# 1_MIAN.net
KiCad netlist of a schematic drawn in Altium Designer
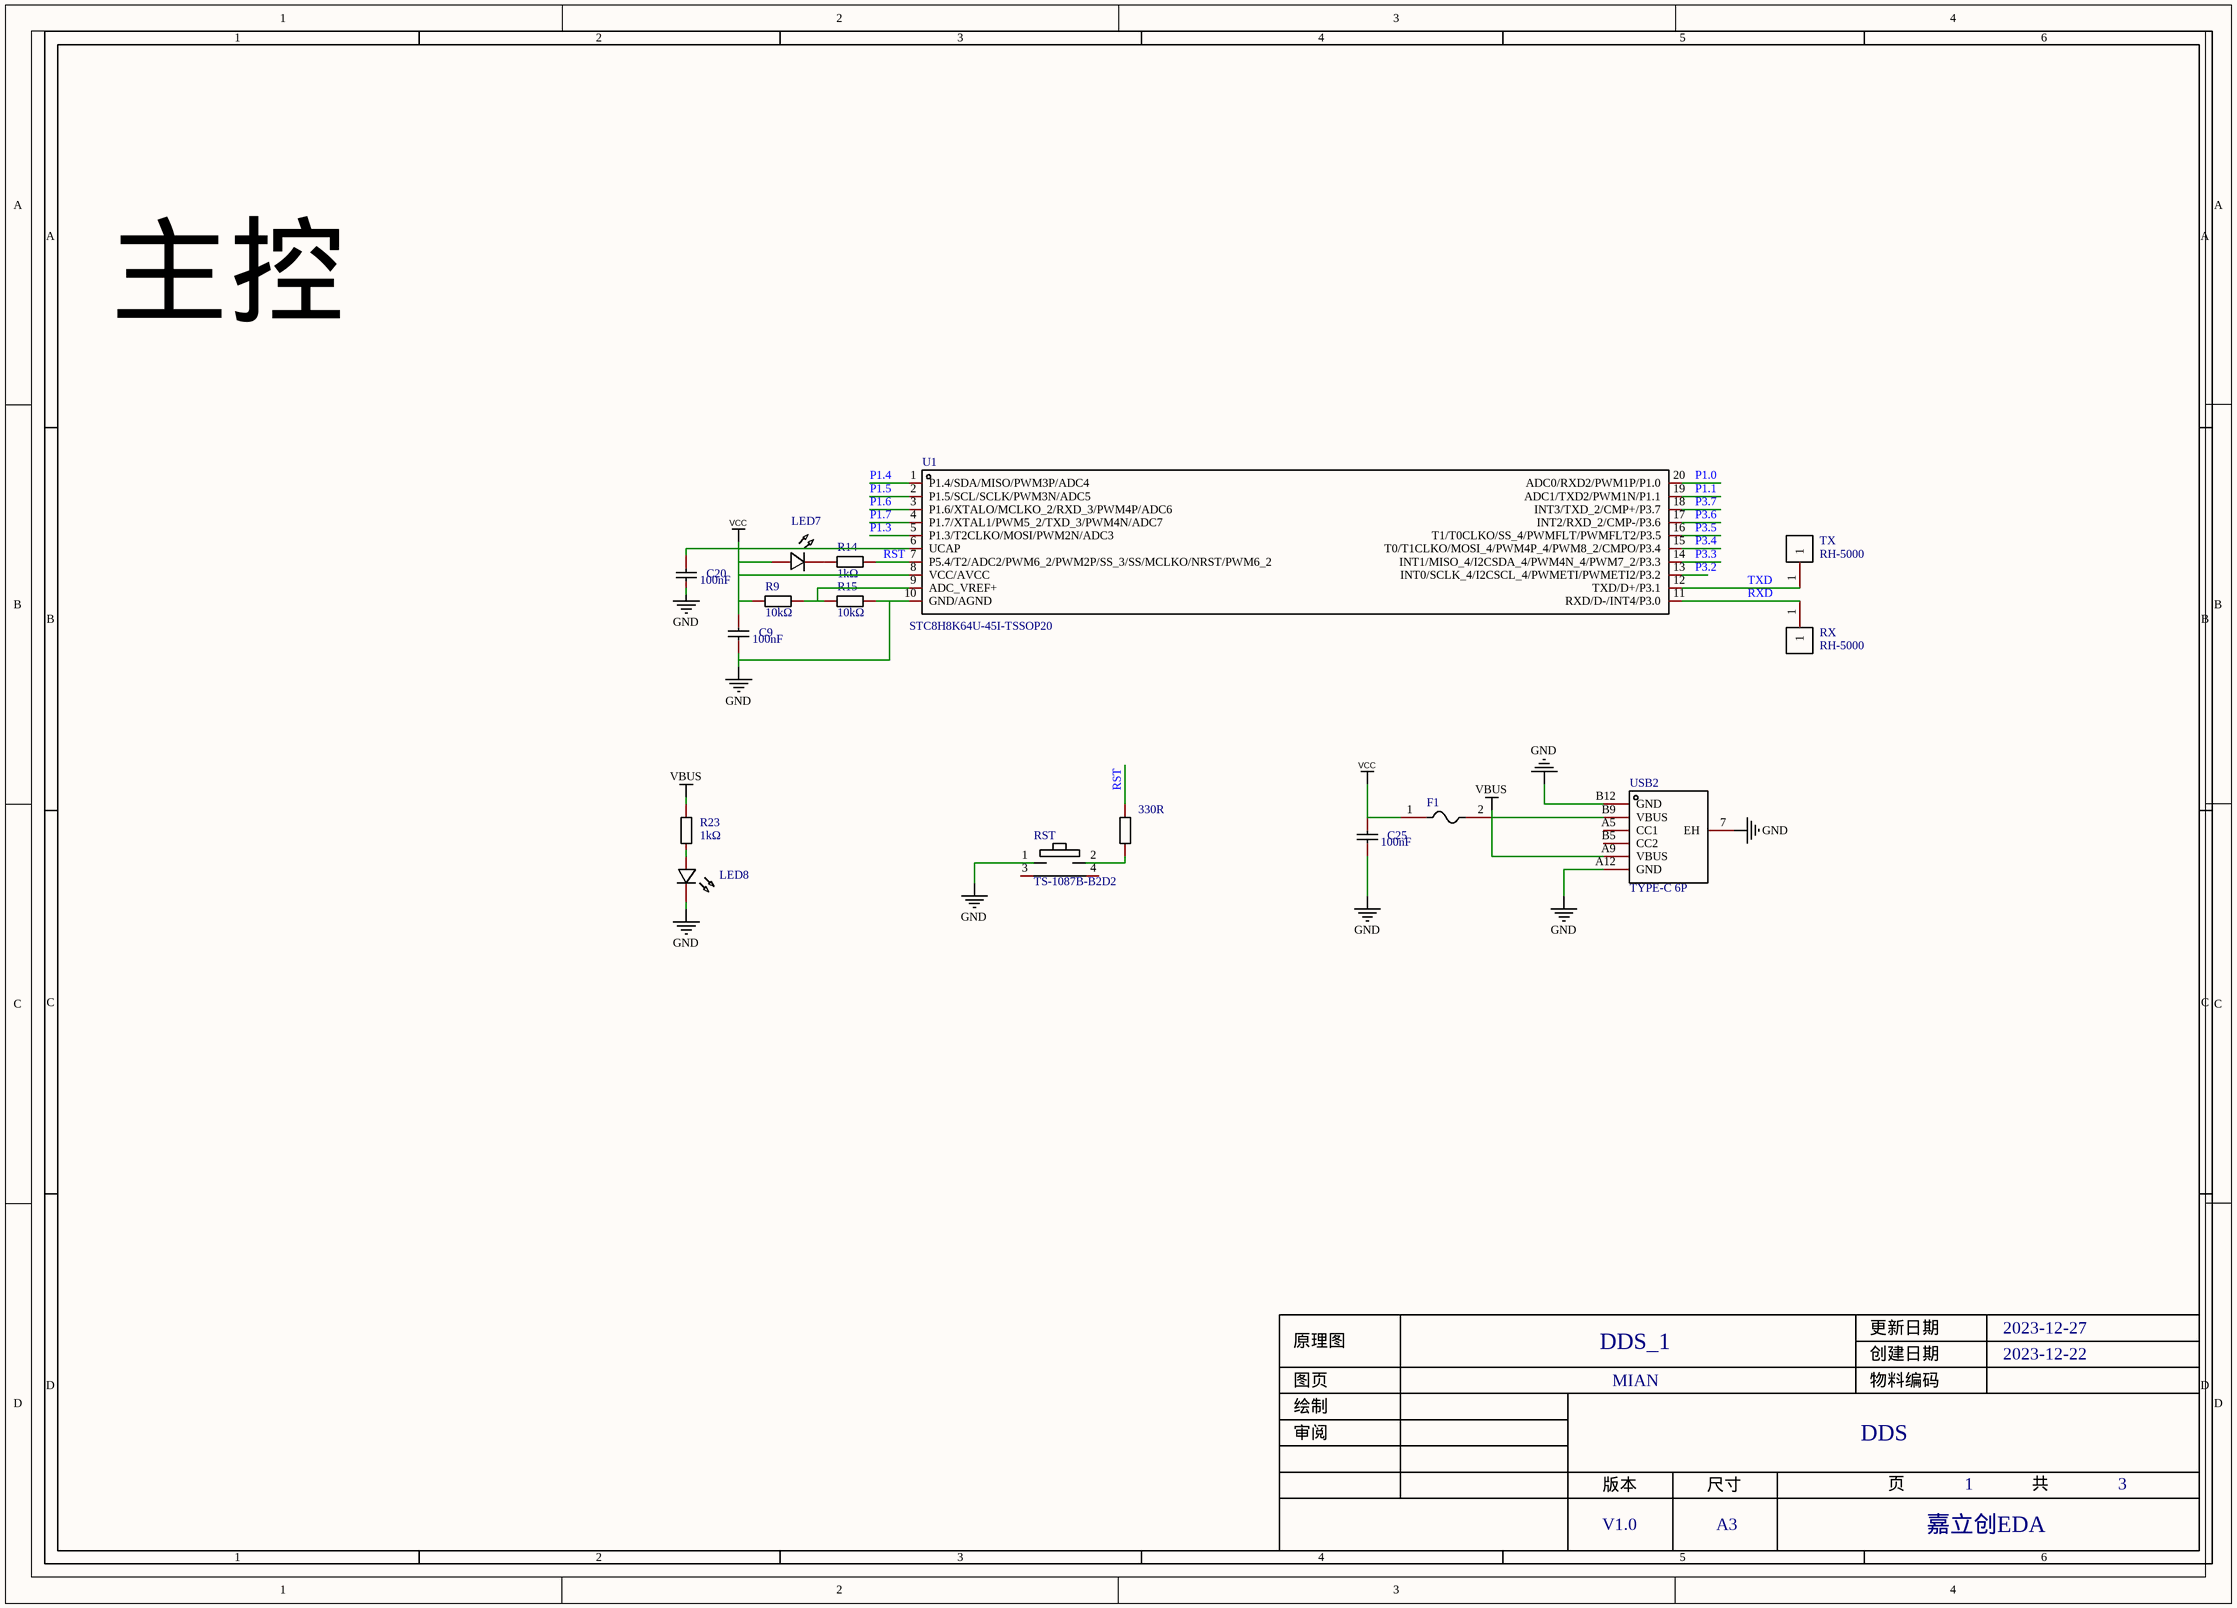
[diagram p0: 1_MIAN.schdoc]

(export (version "E")
  (design (tool "Eeschema 10.0.6"))
  (components
    (comp (ref "C9")
      (value "100nF")
      (description "容值:100nF;精度:±10%;额定电压:50V;材质(温度系数):X7R;")
      (fields
        (field (name "NAME") "100nF")
        (field (name "MANUFACTURER") "FH(风华)")
        (field (name "MANUFACTURER PART") "0805B104K500NT")
      )
      (libsource (lib "altium-import") (part "root_1_0805B104K500NT_"))
    )
    (comp (ref "C20")
      (value "100nF")
      (description "容值:100nF;精度:±10%;额定电压:50V;材质(温度系数):X7R;")
      (fields
        (field (name "NAME") "100nF")
        (field (name "MANUFACTURER") "FH(风华)")
        (field (name "MANUFACTURER PART") "0805B104K500NT")
      )
      (libsource (lib "altium-import") (part "root_1_0805B104K500NT_"))
    )
    (comp (ref "C25")
      (value "100nF")
      (description "容值:100nF;精度:±10%;额定电压:50V;材质(温度系数):X7R;")
      (fields
        (field (name "NAME") "100nF")
        (field (name "MANUFACTURER") "FH(风华)")
        (field (name "MANUFACTURER PART") "0805B104K500NT")
      )
      (libsource (lib "altium-import") (part "root_1_0805B104K500NT_"))
    )
    (comp (ref "F1")
      (value "nSMD010")
      (description "最大电压:60V;最大电流:40A;保持电流:100mA;跳闸电流:250mA;")
      (fields (field (name "MANUFACTURER") "台湾陆海"))
      (libsource (lib "altium-import") (part "root_0_nSMD010_"))
    )
    (comp (ref "LED7") (value "LED_B") (libsource (lib "altium-import") (part "root_0_LED_B_")))
    (comp (ref "LED8") (value "LED_B") (libsource (lib "altium-import") (part "root_3_LED_B_")))
    (comp (ref "R5")
      (value "330R")
      (description "阻值:1kΩ;精度:±1%;功率:125mW;温度系数:±100ppm/℃;电阻类型:厚膜电阻;")
      (fields
        (field (name "MANUFACTURER") "UNI-ROYAL(厚声)")
        (field (name "MANUFACTURER PART") "0805W8F1001T5E")
      )
      (libsource (lib "altium-import") (part "root_1_0805W8F1001T5E_"))
    )
    (comp (ref "R9")
      (value "10kΩ")
      (description "阻值:1kΩ;精度:±1%;功率:125mW;温度系数:±100ppm/℃;电阻类型:厚膜电阻;")
      (fields
        (field (name "NAME") "10kΩ")
        (field (name "MANUFACTURER") "UNI-ROYAL(厚声)")
        (field (name "MANUFACTURER PART") "0805W8F1001T5E")
      )
      (libsource (lib "altium-import") (part "root_0_0805W8F1001T5E_"))
    )
    (comp (ref "R14")
      (value "1kΩ")
      (description "阻值:1kΩ;精度:±1%;功率:125mW;温度系数:±100ppm/℃;电阻类型:厚膜电阻;")
      (fields
        (field (name "NAME") "1kΩ")
        (field (name "MANUFACTURER") "UNI-ROYAL(厚声)")
        (field (name "MANUFACTURER PART") "0805W8F1001T5E")
      )
      (libsource (lib "altium-import") (part "root_0_0805W8F1001T5E_"))
    )
    (comp (ref "R15")
      (value "10kΩ")
      (description "阻值:1kΩ;精度:±1%;功率:125mW;温度系数:±100ppm/℃;电阻类型:厚膜电阻;")
      (fields
        (field (name "NAME") "10kΩ")
        (field (name "MANUFACTURER") "UNI-ROYAL(厚声)")
        (field (name "MANUFACTURER PART") "0805W8F1001T5E")
      )
      (libsource (lib "altium-import") (part "root_0_0805W8F1001T5E_"))
    )
    (comp (ref "R23")
      (value "1kΩ")
      (description "阻值:1kΩ;精度:±1%;功率:125mW;温度系数:±100ppm/℃;电阻类型:厚膜电阻;")
      (fields
        (field (name "NAME") "1kΩ")
        (field (name "MANUFACTURER") "UNI-ROYAL(厚声)")
        (field (name "MANUFACTURER PART") "0805W8F1001T5E")
      )
      (libsource (lib "altium-import") (part "root_1_0805W8F1001T5E_"))
    )
    (comp (ref "RST")
      (value "TS-1087B-B2D2")
      (description "电路结构:单刀单掷;按钮作用方向:侧面触动;致动器样式:矩形按钮;照明颜色:-;作用力:180gf ±30gf;开关高度:3.5mm;")
      (fields (field (name "NAME") "TS-1087B-B2D2") (field (name "MANUFACTURER") "Yuandi(元迪)"))
      (libsource (lib "altium-import") (part "root_0_TS-1087B-B2D2_"))
    )
    (comp (ref "RX")
      (value "RH-5000")
      (description "100x80mm")
      (fields (field (name "NAME") "RH-5000") (field (name "MANUFACTURER") "荣和"))
      (libsource (lib "altium-import") (part "root_1_RH-5000_"))
    )
    (comp (ref "TX")
      (value "RH-5000")
      (description "100x80mm")
      (fields (field (name "NAME") "RH-5000") (field (name "MANUFACTURER") "荣和"))
      (libsource (lib "altium-import") (part "root_3_RH-5000_"))
    )
    (comp (ref "U1")
      (value "STC8H8K64U-45I-TSSOP20")
      (fields (field (name "NAME") "STC8H8K64U-45I-TSSOP20") (field (name "MANUFACTURER") "STC(宏晶)"))
      (libsource (lib "altium-import") (part "root_0_STC8H8K64U-45I-TSSOP20_"))
    )
    (comp (ref "USB2")
      (value "TYPE-C 6P")
      (description "连接器类型:Type-C;标准:-;公母:母;端口数量:1;触点数量:6P;安装方式:卧贴;额定电流 - 电源:-;工作温度范围:-40℃~+85℃;")
      (fields (field (name "NAME") "TYPE-C 6P") (field (name "MANUFACTURER") "SHOU HAN(首韩)"))
      (libsource (lib "altium-import") (part "root_0_TYPE-C 6P_"))
    )
  )
  (nets
    (net (code "1") (name "/P1.0") (class "Default")
      (node (ref "U1") (pin "20") (pinfunction "ADC0/RXD2/PWM1P/P1.0_20") (pintype "passive"))
    )
    (net (code "2") (name "/P1.1") (class "Default")
      (node (ref "U1") (pin "19") (pinfunction "ADC1/TXD2/PWM1N/P1.1_19") (pintype "passive"))
    )
    (net (code "3") (name "/P1.3") (class "Default")
      (node (ref "U1") (pin "5") (pinfunction "P1.3/T2CLKO/MOSI/PWM2N/ADC3_5") (pintype "passive"))
    )
    (net (code "4") (name "/P1.4") (class "Default")
      (node (ref "U1") (pin "1") (pinfunction "P1.4/SDA/MISO/PWM3P/ADC4_1") (pintype "passive"))
    )
    (net (code "5") (name "/P1.5") (class "Default")
      (node (ref "U1") (pin "2") (pinfunction "P1.5/SCL/SCLK/PWM3N/ADC5_2") (pintype "passive"))
    )
    (net (code "6") (name "/P1.6") (class "Default")
      (node (ref "U1") (pin "3") (pinfunction "P1.6/XTALO/MCLKO_2/RXD_3/PWM4P/ADC6_3") (pintype "passive"))
    )
    (net (code "7") (name "/P1.7") (class "Default")
      (node (ref "U1") (pin "4") (pinfunction "P1.7/XTAL1/PWM5_2/TXD_3/PWM4N/ADC7_4") (pintype "passive"))
    )
    (net (code "8") (name "/P3.2") (class "Default")
      (node (ref "U1") (pin "13") (pinfunction "INT0/SCLK_4/I2CSCL_4/PWMETI/PWMETI2/P3.2_13") (pintype "passive"))
    )
    (net (code "9") (name "/P3.3") (class "Default")
      (node (ref "U1") (pin "14") (pinfunction "INT1/MISO_4/I2CSDA_4/PWM4N_4/PWM7_2/P3.3_14") (pintype "passive"))
    )
    (net (code "10") (name "/P3.4") (class "Default")
      (node (ref "U1") (pin "15") (pinfunction "T0/T1CLKO/MOSI_4/PWM4P_4/PWM8_2/CMPO/P3.4_15") (pintype "passive"))
    )
    (net (code "11") (name "/P3.5") (class "Default")
      (node (ref "U1") (pin "16") (pinfunction "T1/T0CLKO/SS_4/PWMFLT/PWMFLT2/P3.5_16") (pintype "passive"))
    )
    (net (code "12") (name "/P3.6") (class "Default")
      (node (ref "U1") (pin "17") (pinfunction "INT2/RXD_2/CMP-/P3.6_17") (pintype "passive"))
    )
    (net (code "13") (name "/P3.7") (class "Default")
      (node (ref "U1") (pin "18") (pinfunction "INT3/TXD_2/CMP+/P3.7_18") (pintype "passive"))
    )
    (net (code "14") (name "/RST") (class "Default")
      (node (ref "R14") (pin "2") (pinfunction "2_2") (pintype "passive"))
      (node (ref "R5") (pin "2") (pinfunction "2_2") (pintype "passive"))
      (node (ref "U1") (pin "7") (pinfunction "P5.4/T2/ADC2/PWM6_2/PWM2P/SS_3/SS/MCLKO/NRST/PWM6_2_7") (pintype "passive"))
    )
    (net (code "15") (name "/RXD") (class "Default")
      (node (ref "RX") (pin "1") (pinfunction "1_1") (pintype "passive"))
      (node (ref "U1") (pin "11") (pinfunction "RXD/D-/INT4/P3.0_11") (pintype "passive"))
    )
    (net (code "16") (name "/TXD") (class "Default")
      (node (ref "TX") (pin "1") (pinfunction "1_1") (pintype "passive"))
      (node (ref "U1") (pin "12") (pinfunction "TXD/D+/P3.1_12") (pintype "passive"))
    )
    (net (code "17") (name "GND") (class "Default")
      (node (ref "C20") (pin "1") (pinfunction "1_1") (pintype "passive"))
      (node (ref "C25") (pin "1") (pinfunction "1_1") (pintype "passive"))
      (node (ref "C9") (pin "1") (pinfunction "1_1") (pintype "passive"))
      (node (ref "LED8") (pin "1") (pinfunction "C_1") (pintype "passive"))
      (node (ref "R15") (pin "2") (pinfunction "2_2") (pintype "passive"))
      (node (ref "RST") (pin "1") (pinfunction "1_1") (pintype "passive"))
      (node (ref "U1") (pin "10") (pinfunction "GND/AGND_10") (pintype "passive"))
      (node (ref "USB2") (pin "7") (pinfunction "EH_7") (pintype "passive"))
      (node (ref "USB2") (pin "A12") (pinfunction "GND_A12") (pintype "passive"))
      (node (ref "USB2") (pin "B12") (pinfunction "GND_B12") (pintype "passive"))
    )
    (net (code "18") (name "Net-(LED7-C)") (class "Default")
      (node (ref "LED7") (pin "1") (pinfunction "C_1") (pintype "passive"))
      (node (ref "R14") (pin "1") (pinfunction "1_1") (pintype "passive"))
    )
    (net (code "19") (name "Net-(LED8-A)") (class "Default")
      (node (ref "LED8") (pin "2") (pinfunction "A_2") (pintype "passive"))
      (node (ref "R23") (pin "1") (pinfunction "1_1") (pintype "passive"))
    )
    (net (code "20") (name "Net-(R5-Pad1)") (class "Default")
      (node (ref "R5") (pin "1") (pinfunction "1_1") (pintype "passive"))
      (node (ref "RST") (pin "2") (pinfunction "2_2") (pintype "passive"))
    )
    (net (code "21") (name "Net-(U1-ADC_VREF+)") (class "Default")
      (node (ref "R15") (pin "1") (pinfunction "1_1") (pintype "passive"))
      (node (ref "R9") (pin "2") (pinfunction "2_2") (pintype "passive"))
      (node (ref "U1") (pin "9") (pinfunction "ADC_VREF+_9") (pintype "passive"))
    )
    (net (code "22") (name "Net-(U1-UCAP)") (class "Default")
      (node (ref "C20") (pin "2") (pinfunction "2_2") (pintype "passive"))
      (node (ref "U1") (pin "6") (pinfunction "UCAP_6") (pintype "passive"))
    )
    (net (code "23") (name "VBUS") (class "Default")
      (node (ref "F1") (pin "2") (pinfunction "2_2") (pintype "passive"))
      (node (ref "R23") (pin "2") (pinfunction "2_2") (pintype "passive"))
      (node (ref "USB2") (pin "A9") (pinfunction "VBUS_A9") (pintype "passive"))
      (node (ref "USB2") (pin "B9") (pinfunction "VBUS_B9") (pintype "passive"))
    )
    (net (code "24") (name "VCC") (class "Default")
      (node (ref "C25") (pin "2") (pinfunction "2_2") (pintype "passive"))
      (node (ref "C9") (pin "2") (pinfunction "2_2") (pintype "passive"))
      (node (ref "F1") (pin "1") (pinfunction "1_1") (pintype "passive"))
      (node (ref "LED7") (pin "2") (pinfunction "A_2") (pintype "passive"))
      (node (ref "R9") (pin "1") (pinfunction "1_1") (pintype "passive"))
      (node (ref "U1") (pin "8") (pinfunction "VCC/AVCC_8") (pintype "passive"))
    )
    (net (code "25") (name "unconnected-(RST-Pad3)") (class "Default")
      (node (ref "RST") (pin "3") (pinfunction "3_3") (pintype "passive"))
    )
    (net (code "26") (name "unconnected-(RST-Pad4)") (class "Default")
      (node (ref "RST") (pin "4") (pinfunction "4_4") (pintype "passive"))
    )
    (net (code "27") (name "unconnected-(USB2-CC1-PadA5)") (class "Default")
      (node (ref "USB2") (pin "A5") (pinfunction "CC1_A5") (pintype "passive"))
    )
    (net (code "28") (name "unconnected-(USB2-CC2-PadB5)") (class "Default")
      (node (ref "USB2") (pin "B5") (pinfunction "CC2_B5") (pintype "passive"))
    )
  )
)
